# Powalowski_sch.net
KiCad netlist of a schematic drawn in EAGLE
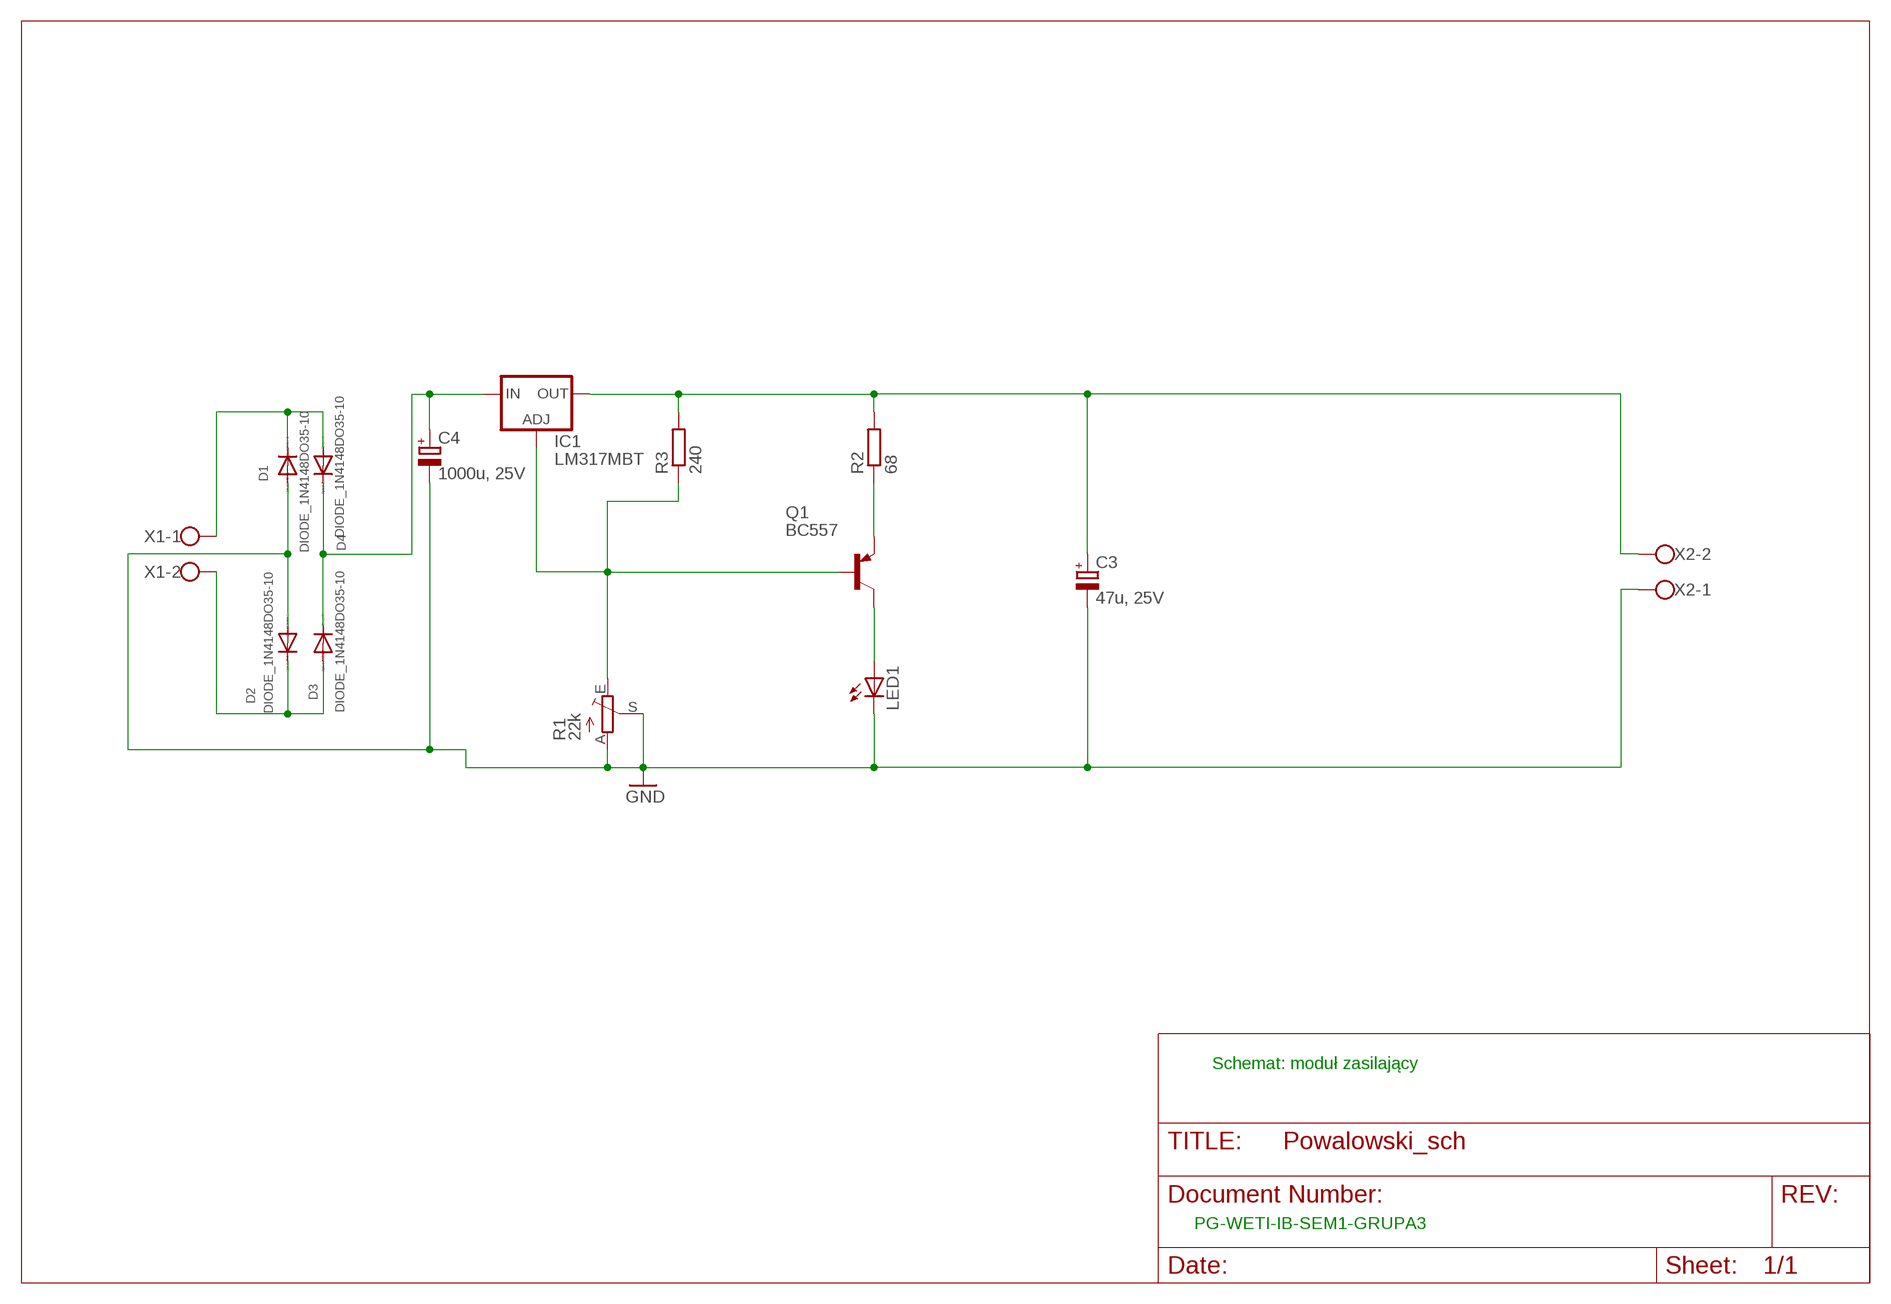
[diagram p0: schematic, sheet 1]

(export (version "E")
  (design (tool "Eeschema 10.0.6"))
  (components
    (comp (ref "C3")
      (value "47u, 25V")
      (footprint "eagle-import:E7,5-16")
      (libsource (lib "eagle-import") (part "CPOL-EUE7.5-16"))
    )
    (comp (ref "C4")
      (value "1000u, 25V")
      (footprint "eagle-import:E7,5-16")
      (libsource (lib "eagle-import") (part "CPOL-EUE7.5-16"))
    )
    (comp (ref "D1")
      (value "DIODE_1N4148DO35-10")
      (footprint "eagle-import:DIODE_DO35-10")
      (libsource (lib "eagle-import") (part "DIODE_1N4148DO35-10"))
    )
    (comp (ref "D2")
      (value "DIODE_1N4148DO35-10")
      (footprint "eagle-import:DIODE_DO35-10")
      (libsource (lib "eagle-import") (part "DIODE_1N4148DO35-10"))
    )
    (comp (ref "D3")
      (value "DIODE_1N4148DO35-10")
      (footprint "eagle-import:DIODE_DO35-10")
      (libsource (lib "eagle-import") (part "DIODE_1N4148DO35-10"))
    )
    (comp (ref "D4")
      (value "DIODE_1N4148DO35-10")
      (footprint "eagle-import:DIODE_DO35-10")
      (libsource (lib "eagle-import") (part "DIODE_1N4148DO35-10"))
    )
    (comp (ref "IC1")
      (value "LM317MBT")
      (footprint "eagle-import:TO220L1")
      (libsource (lib "eagle-import") (part "LM317?MBT"))
    )
    (comp (ref "LED1")
      (value "LED_LED5MM")
      (footprint "eagle-import:LED_LED5MM")
      (libsource (lib "eagle-import") (part "LED_LED5MM"))
    )
    (comp (ref "Q1")
      (value "BC557")
      (footprint "eagle-import:TO92-EBC")
      (libsource (lib "eagle-import") (part "BC557"))
    )
    (comp (ref "R1")
      (value "22k")
      (footprint "eagle-import:RS3")
      (libsource (lib "eagle-import") (part "TRIM_EU-RS3"))
    )
    (comp (ref "R2")
      (value "68")
      (footprint "eagle-import:R1210")
      (libsource (lib "eagle-import") (part "R-EU_R1210"))
    )
    (comp (ref "R3")
      (value "240")
      (footprint "eagle-import:R1210")
      (libsource (lib "eagle-import") (part "R-EU_R1210"))
    )
    (comp (ref "X1")
      (value "W237-102")
      (footprint "eagle-import:W237-102")
      (fields (field (name "MPN") "237-102"))
      (libsource (lib "eagle-import") (part "W237-102"))
    )
    (comp (ref "X2")
      (value "W237-102")
      (footprint "eagle-import:W237-102")
      (fields (field (name "MPN") "237-102"))
      (libsource (lib "eagle-import") (part "W237-102"))
    )
  )
  (nets
    (net (code "1") (name "GND") (class "Default")
      (node (ref "C3") (pin "-") (pinfunction "-_-") (pintype "passive"))
      (node (ref "C4") (pin "-") (pinfunction "-_-") (pintype "passive"))
      (node (ref "D1") (pin "A") (pinfunction "A_A") (pintype "passive"))
      (node (ref "D2") (pin "A") (pinfunction "A_A") (pintype "passive"))
      (node (ref "LED1") (pin "K") (pinfunction "C_K") (pintype "passive"))
      (node (ref "R1") (pin "A") (pinfunction "A_A") (pintype "passive"))
      (node (ref "R1") (pin "S") (pinfunction "S_S") (pintype "passive"))
      (node (ref "X2") (pin "1") (pinfunction "KL_1") (pintype "passive"))
    )
    (net (code "2") (name "Net-(IC1-ADJ)") (class "Default")
      (node (ref "IC1") (pin "1") (pinfunction "ADJ_1") (pintype "input"))
      (node (ref "Q1") (pin "B") (pinfunction "B_B") (pintype "passive"))
      (node (ref "R1") (pin "E") (pinfunction "E_E") (pintype "passive"))
      (node (ref "R3") (pin "1") (pinfunction "1_1") (pintype "passive"))
    )
    (net (code "3") (name "Net-(IC1-IN)") (class "Default")
      (node (ref "C4") (pin "+") (pinfunction "+_+") (pintype "passive"))
      (node (ref "D3") (pin "C") (pinfunction "C_C") (pintype "passive"))
      (node (ref "D4") (pin "C") (pinfunction "C_C") (pintype "passive"))
      (node (ref "IC1") (pin "3") (pinfunction "IN_3") (pintype "input"))
    )
    (net (code "4") (name "Net-(IC1-OUT)") (class "Default")
      (node (ref "C3") (pin "+") (pinfunction "+_+") (pintype "passive"))
      (node (ref "IC1") (pin "2") (pinfunction "OUT_2") (pintype "passive"))
      (node (ref "R2") (pin "2") (pinfunction "2_2") (pintype "passive"))
      (node (ref "R3") (pin "2") (pinfunction "2_2") (pintype "passive"))
      (node (ref "X2") (pin "2") (pinfunction "KL_2") (pintype "passive"))
    )
    (net (code "5") (name "Net-(LED1-PadA)") (class "Default")
      (node (ref "LED1") (pin "A") (pinfunction "A_A") (pintype "passive"))
      (node (ref "Q1") (pin "C") (pinfunction "C_C") (pintype "passive"))
    )
    (net (code "6") (name "Net-(Q1-PadE)") (class "Default")
      (node (ref "Q1") (pin "E") (pinfunction "E_E") (pintype "passive"))
      (node (ref "R2") (pin "1") (pinfunction "1_1") (pintype "passive"))
    )
    (net (code "7") (name "Net-(X1A-KL)") (class "Default")
      (node (ref "D1") (pin "C") (pinfunction "C_C") (pintype "passive"))
      (node (ref "D4") (pin "A") (pinfunction "A_A") (pintype "passive"))
      (node (ref "X1") (pin "1") (pinfunction "KL_1") (pintype "passive"))
    )
    (net (code "8") (name "Net-(X1B-KL)") (class "Default")
      (node (ref "D2") (pin "C") (pinfunction "C_C") (pintype "passive"))
      (node (ref "D3") (pin "A") (pinfunction "A_A") (pintype "passive"))
      (node (ref "X1") (pin "2") (pinfunction "KL_2") (pintype "passive"))
    )
  )
)
